# Power.net
KiCad netlist of a schematic drawn in Altium Designer
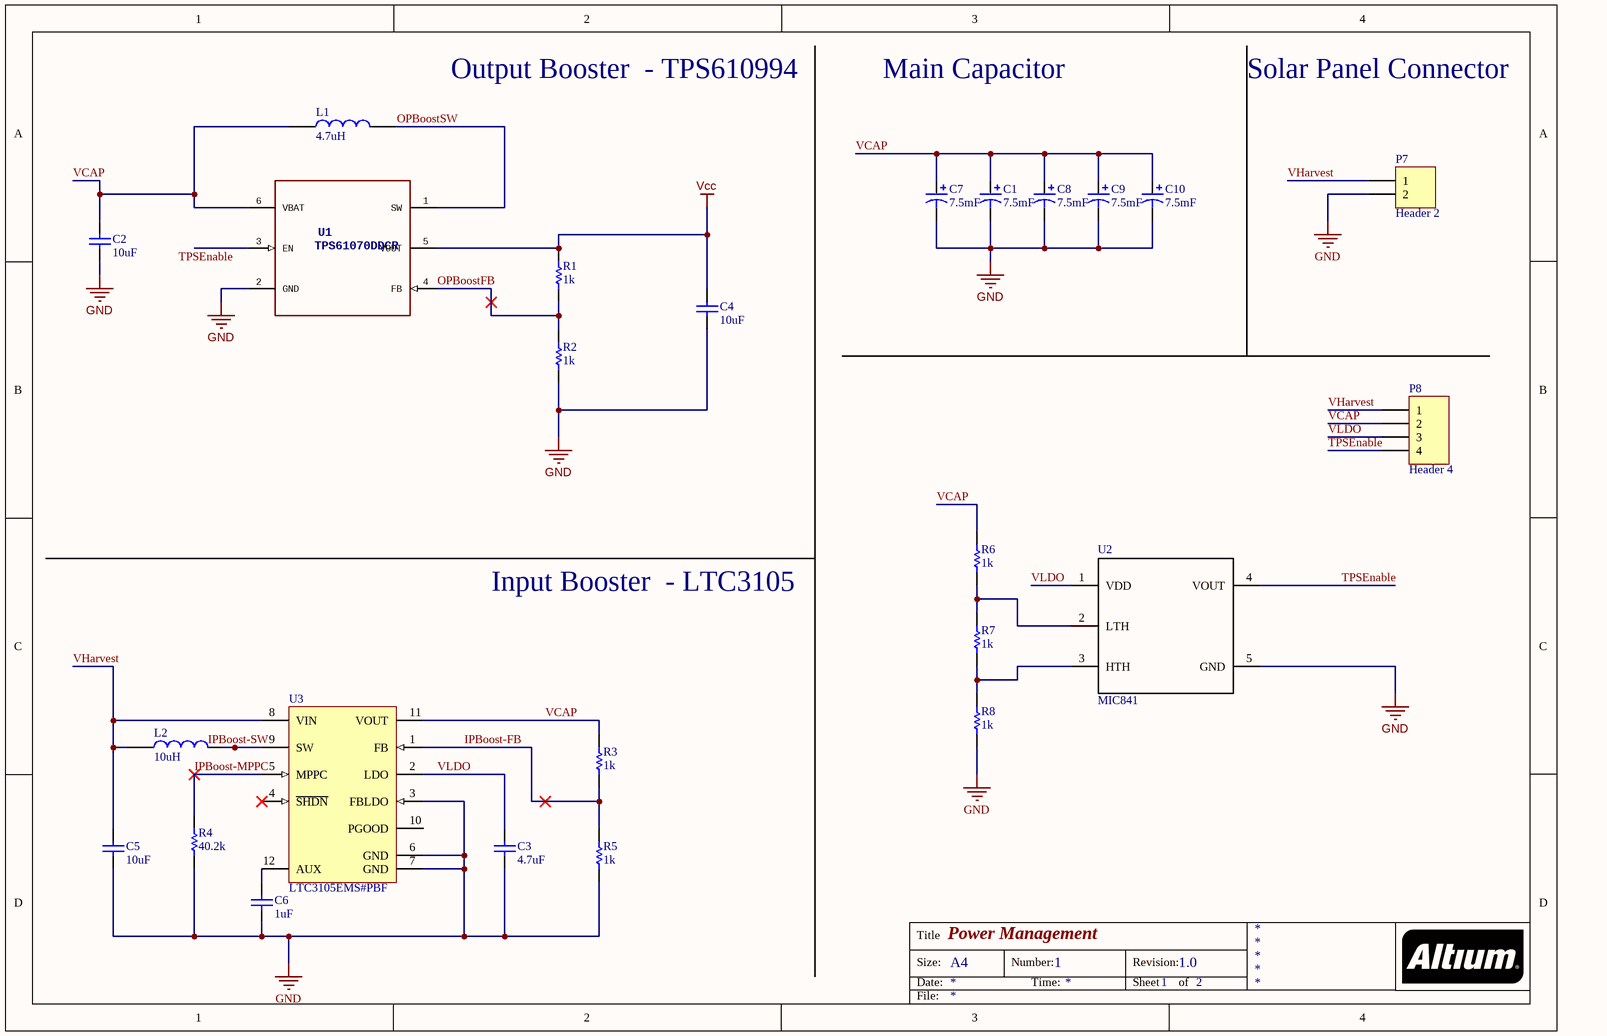
[diagram p0: Power.SchDoc]

(export (version "E")
  (design (tool "Eeschema 10.0.6"))
  (components
    (comp (ref "C1")
      (value "7.5mF")
      (footprint "Sprite:CAP_CPH3225A")
      (description "Polarized Capacitor")
      (fields (field (name "Comment") "Cap - Polarized"))
      (libsource (lib "DRP_Basic_2014") (part "Cap - Polarized"))
    )
    (comp (ref "C2")
      (value "10uF")
      (footprint "0805")
      (description "Ceramic Capacitor (Surface Mount)")
      (fields (field (name "MANUFACTURER") "Generic Ceramic Chip Cap (TBD)") (field (name "Comment") "Cap"))
      (libsource (lib "DRP_Basic_2014") (part "Cap"))
    )
    (comp (ref "C3")
      (value "4.7uF")
      (footprint "0805")
      (description "Ceramic Capacitor (Surface Mount)")
      (fields (field (name "MANUFACTURER") "Generic Ceramic Chip Cap (TBD)") (field (name "Comment") "Cap"))
      (libsource (lib "DRP_Basic_2014") (part "Cap"))
    )
    (comp (ref "C4")
      (value "10uF")
      (footprint "0805")
      (description "Ceramic Capacitor (Surface Mount)")
      (fields (field (name "MANUFACTURER") "Generic Ceramic Chip Cap (TBD)") (field (name "Comment") "Cap"))
      (libsource (lib "DRP_Basic_2014") (part "Cap"))
    )
    (comp (ref "C5")
      (value "10uF")
      (footprint "0805")
      (description "Ceramic Capacitor (Surface Mount)")
      (fields (field (name "MANUFACTURER") "Generic Ceramic Chip Cap (TBD)") (field (name "Comment") "Cap"))
      (libsource (lib "DRP_Basic_2014") (part "Cap"))
    )
    (comp (ref "C6")
      (value "1uF")
      (footprint "0805")
      (description "Ceramic Capacitor (Surface Mount)")
      (fields (field (name "MANUFACTURER") "Generic Ceramic Chip Cap (TBD)") (field (name "Comment") "Cap"))
      (libsource (lib "DRP_Basic_2014") (part "Cap"))
    )
    (comp (ref "C7")
      (value "7.5mF")
      (footprint "Sprite:CAP_CPH3225A")
      (description "Polarized Capacitor")
      (fields (field (name "Comment") "Cap - Polarized"))
      (libsource (lib "DRP_Basic_2014") (part "Cap - Polarized"))
    )
    (comp (ref "C8")
      (value "7.5mF")
      (footprint "Sprite:CAP_CPH3225A")
      (description "Polarized Capacitor")
      (fields (field (name "Comment") "Cap - Polarized"))
      (libsource (lib "DRP_Basic_2014") (part "Cap - Polarized"))
    )
    (comp (ref "C9")
      (value "7.5mF")
      (footprint "Sprite:CAP_CPH3225A")
      (description "Polarized Capacitor")
      (fields (field (name "Comment") "Cap - Polarized"))
      (libsource (lib "DRP_Basic_2014") (part "Cap - Polarized"))
    )
    (comp (ref "C10")
      (value "7.5mF")
      (footprint "Sprite:CAP_CPH3225A")
      (description "Polarized Capacitor")
      (fields (field (name "Comment") "Cap - Polarized"))
      (libsource (lib "DRP_Basic_2014") (part "Cap - Polarized"))
    )
    (comp (ref "L1")
      (value "4.7uH")
      (footprint "MIC841:1008")
      (description "Power Inductor for DC-DC convters (RF switching freq)")
      (fields (field (name "Comment") "Ind"))
      (libsource (lib "MIC841") (part "Ind - Power"))
    )
    (comp (ref "L2")
      (value "10uH")
      (footprint "MIC841:1008")
      (description "Power Inductor for DC-DC convters (RF switching freq)")
      (fields (field (name "Comment") "Ind"))
      (libsource (lib "MIC841") (part "Ind - Power"))
    )
    (comp (ref "P7")
      (value "Header 2")
      (footprint "HDR1X2")
      (description "Header, 2-Pin")
      (fields (field (name "PUBLISHER") "Altium Limited"))
      (libsource (lib "Miscellaneous Connectors") (part "Header 2"))
    )
    (comp (ref "P8")
      (value "Header 4")
      (footprint "HDR1X4")
      (description "Header, 4-Pin")
      (fields (field (name "PUBLISHER") "Altium Limited"))
      (libsource (lib "Miscellaneous Connectors") (part "Header 4"))
    )
    (comp (ref "R1")
      (value "1k")
      (footprint "0805")
      (description "Chip Resistor (Surface Mount)")
      (fields (field (name "MANUFACTURER") "Generic Chip Res (TBD)") (field (name "Comment") "Res"))
      (libsource (lib "DRP_Basic_2014") (part "Res"))
    )
    (comp (ref "R2")
      (value "1k")
      (footprint "0805")
      (description "Chip Resistor (Surface Mount)")
      (fields (field (name "MANUFACTURER") "Generic Chip Res (TBD)") (field (name "Comment") "Res"))
      (libsource (lib "DRP_Basic_2014") (part "Res"))
    )
    (comp (ref "R3")
      (value "1k")
      (footprint "0805")
      (description "Chip Resistor (Surface Mount)")
      (fields (field (name "MANUFACTURER") "Generic Chip Res (TBD)") (field (name "Comment") "Res"))
      (libsource (lib "DRP_Basic_2014") (part "Res"))
    )
    (comp (ref "R4")
      (value "40.2k")
      (footprint "0805")
      (description "Chip Resistor (Surface Mount)")
      (fields (field (name "MANUFACTURER") "Generic Chip Res (TBD)") (field (name "Comment") "Res"))
      (libsource (lib "DRP_Basic_2014") (part "Res"))
    )
    (comp (ref "R5")
      (value "1k")
      (footprint "0805")
      (description "Chip Resistor (Surface Mount)")
      (fields (field (name "MANUFACTURER") "Generic Chip Res (TBD)") (field (name "Comment") "Res"))
      (libsource (lib "DRP_Basic_2014") (part "Res"))
    )
    (comp (ref "R6")
      (value "1k")
      (footprint "0805")
      (description "Chip Resistor (Surface Mount)")
      (fields (field (name "MANUFACTURER") "Generic Chip Res (TBD)") (field (name "Comment") "Res"))
      (libsource (lib "DRP_Basic_2014") (part "Res"))
    )
    (comp (ref "R7")
      (value "1k")
      (footprint "0805")
      (description "Chip Resistor (Surface Mount)")
      (fields (field (name "MANUFACTURER") "Generic Chip Res (TBD)") (field (name "Comment") "Res"))
      (libsource (lib "DRP_Basic_2014") (part "Res"))
    )
    (comp (ref "R8")
      (value "1k")
      (footprint "0805")
      (description "Chip Resistor (Surface Mount)")
      (fields (field (name "MANUFACTURER") "Generic Chip Res (TBD)") (field (name "Comment") "Res"))
      (libsource (lib "DRP_Basic_2014") (part "Res"))
    )
    (comp (ref "U1")
      (value "TPS61070DDCR")
      (footprint "DDC0006A_N")
      (fields (field (name "MANUFACTURER") "Texas Instruments") (field (name "PARTNUMBER") "TPS61070DDC"))
      (libsource (lib "TPS61070") (part "TPS61070DDCR"))
    )
    (comp (ref "U2") (value "MIC841") (footprint "MIC841:SC-70-5") (libsource (lib "MIC841") (part "MIC841")))
    (comp (ref "U3")
      (value "LTC3105EMS#PBF")
      (footprint "LT-MS-12_N")
      (fields (field (name "MANUFACTURER") "Linear Technology"))
      (libsource (lib "Altium Content Vault") (part "LT-LTC3105-MS-12"))
    )
  )
  (nets
    (net (code "1") (name "/IPBoost-FB") (class "Default")
      (node (ref "R3") (pin "2") (pinfunction "2_2") (pintype "passive"))
      (node (ref "R5") (pin "1") (pinfunction "1_1") (pintype "passive"))
      (node (ref "U3") (pin "1") (pinfunction "FB_1") (pintype "input"))
    )
    (net (code "2") (name "/IPBoost-MPPC") (class "Default")
      (node (ref "R4") (pin "1") (pinfunction "1_1") (pintype "passive"))
      (node (ref "U3") (pin "5") (pinfunction "MPPC_5") (pintype "input"))
    )
    (net (code "4") (name "/OPBoostFB") (class "Default")
      (node (ref "R1") (pin "1") (pinfunction "1_1") (pintype "passive"))
      (node (ref "R2") (pin "2") (pinfunction "2_2") (pintype "passive"))
      (node (ref "U1") (pin "4") (pinfunction "FB_4") (pintype "input"))
    )
    (net (code "5") (name "/OPBoostSW") (class "Default")
      (node (ref "L1") (pin "2") (pinfunction "2_2") (pintype "passive"))
      (node (ref "U1") (pin "1") (pinfunction "SW_1") (pintype "power_in"))
    )
    (net (code "6") (name "/TPSEnable") (class "Default")
      (node (ref "P8") (pin "4") (pinfunction "4_4") (pintype "passive"))
      (node (ref "U1") (pin "3") (pinfunction "EN_3") (pintype "input"))
      (node (ref "U2") (pin "4") (pinfunction "VOUT_4") (pintype "passive"))
    )
    (net (code "7") (name "/VCAP") (class "Default")
      (node (ref "C1") (pin "1") (pinfunction "1_1") (pintype "passive"))
      (node (ref "C10") (pin "1") (pinfunction "1_1") (pintype "passive"))
      (node (ref "C2") (pin "2") (pinfunction "2_2") (pintype "passive"))
      (node (ref "C7") (pin "1") (pinfunction "1_1") (pintype "passive"))
      (node (ref "C8") (pin "1") (pinfunction "1_1") (pintype "passive"))
      (node (ref "C9") (pin "1") (pinfunction "1_1") (pintype "passive"))
      (node (ref "L1") (pin "1") (pinfunction "1_1") (pintype "passive"))
      (node (ref "P8") (pin "2") (pinfunction "2_2") (pintype "passive"))
      (node (ref "R3") (pin "1") (pinfunction "1_1") (pintype "passive"))
      (node (ref "R6") (pin "2") (pinfunction "2_2") (pintype "passive"))
      (node (ref "U1") (pin "6") (pinfunction "VBAT_6") (pintype "power_in"))
      (node (ref "U3") (pin "11") (pinfunction "VOUT_11") (pintype "power_in"))
    )
    (net (code "8") (name "/VHarvest") (class "Default")
      (node (ref "C5") (pin "2") (pinfunction "2_2") (pintype "passive"))
      (node (ref "L2") (pin "1") (pinfunction "1_1") (pintype "passive"))
      (node (ref "P7") (pin "1") (pinfunction "1_1") (pintype "passive"))
      (node (ref "P8") (pin "1") (pinfunction "1_1") (pintype "passive"))
      (node (ref "U3") (pin "8") (pinfunction "VIN_8") (pintype "power_in"))
    )
    (net (code "9") (name "/VLDO") (class "Default")
      (node (ref "C3") (pin "2") (pinfunction "2_2") (pintype "passive"))
      (node (ref "P8") (pin "3") (pinfunction "3_3") (pintype "passive"))
      (node (ref "U2") (pin "1") (pinfunction "VDD_1") (pintype "passive"))
      (node (ref "U3") (pin "2") (pinfunction "LDO_2") (pintype "power_in"))
    )
    (net (code "10") (name "GND") (class "Default")
      (node (ref "C1") (pin "2") (pinfunction "2_2") (pintype "passive"))
      (node (ref "C10") (pin "2") (pinfunction "2_2") (pintype "passive"))
      (node (ref "C2") (pin "1") (pinfunction "1_1") (pintype "passive"))
      (node (ref "C3") (pin "1") (pinfunction "1_1") (pintype "passive"))
      (node (ref "C4") (pin "1") (pinfunction "1_1") (pintype "passive"))
      (node (ref "C5") (pin "1") (pinfunction "1_1") (pintype "passive"))
      (node (ref "C6") (pin "1") (pinfunction "1_1") (pintype "passive"))
      (node (ref "C7") (pin "2") (pinfunction "2_2") (pintype "passive"))
      (node (ref "C8") (pin "2") (pinfunction "2_2") (pintype "passive"))
      (node (ref "C9") (pin "2") (pinfunction "2_2") (pintype "passive"))
      (node (ref "P7") (pin "2") (pinfunction "2_2") (pintype "passive"))
      (node (ref "R2") (pin "1") (pinfunction "1_1") (pintype "passive"))
      (node (ref "R4") (pin "2") (pinfunction "2_2") (pintype "passive"))
      (node (ref "R5") (pin "2") (pinfunction "2_2") (pintype "passive"))
      (node (ref "R8") (pin "1") (pinfunction "1_1") (pintype "passive"))
      (node (ref "U1") (pin "2") (pinfunction "GND_2") (pintype "power_in"))
      (node (ref "U2") (pin "5") (pinfunction "GND_5") (pintype "passive"))
      (node (ref "U3") (pin "3") (pinfunction "FBLDO_3") (pintype "input"))
      (node (ref "U3") (pin "6") (pinfunction "GND_6") (pintype "power_in"))
      (node (ref "U3") (pin "7") (pinfunction "GND_7") (pintype "power_in"))
    )
    (net (code "11") (name "Net-(U2-HTH)") (class "Default")
      (node (ref "R7") (pin "1") (pinfunction "1_1") (pintype "passive"))
      (node (ref "R8") (pin "2") (pinfunction "2_2") (pintype "passive"))
      (node (ref "U2") (pin "3") (pinfunction "HTH_3") (pintype "passive"))
    )
    (net (code "12") (name "Net-(U2-LTH)") (class "Default")
      (node (ref "R6") (pin "1") (pinfunction "1_1") (pintype "passive"))
      (node (ref "R7") (pin "2") (pinfunction "2_2") (pintype "passive"))
      (node (ref "U2") (pin "2") (pinfunction "LTH_2") (pintype "passive"))
    )
    (net (code "13") (name "Net-(U3-AUX)") (class "Default")
      (node (ref "C6") (pin "2") (pinfunction "2_2") (pintype "passive"))
      (node (ref "U3") (pin "12") (pinfunction "AUX_12") (pintype "power_in"))
    )
    (net (code "14") (name "Net-(U3-SW)") (class "Default")
      (node (ref "L2") (pin "2") (pinfunction "2_2") (pintype "passive"))
      (node (ref "U3") (pin "9") (pinfunction "SW_9") (pintype "power_in"))
    )
    (net (code "15") (name "Vcc") (class "Default")
      (node (ref "C4") (pin "2") (pinfunction "2_2") (pintype "passive"))
      (node (ref "R1") (pin "2") (pinfunction "2_2") (pintype "passive"))
      (node (ref "U1") (pin "5") (pinfunction "VOUT_5") (pintype "power_in"))
    )
    (net (code "16") (name "unconnected-(U3-PGOOD-Pad10)") (class "Default")
      (node (ref "U3") (pin "10") (pinfunction "PGOOD_10") (pintype "open_collector"))
    )
    (net (code "17") (name "unconnected-(U3-~{SHDN}-Pad4)") (class "Default")
      (node (ref "U3") (pin "4") (pinfunction "~{SHDN}_4") (pintype "input+no_connect"))
    )
  )
)
